# 7805.net
KiCad netlist of a schematic drawn in EAGLE
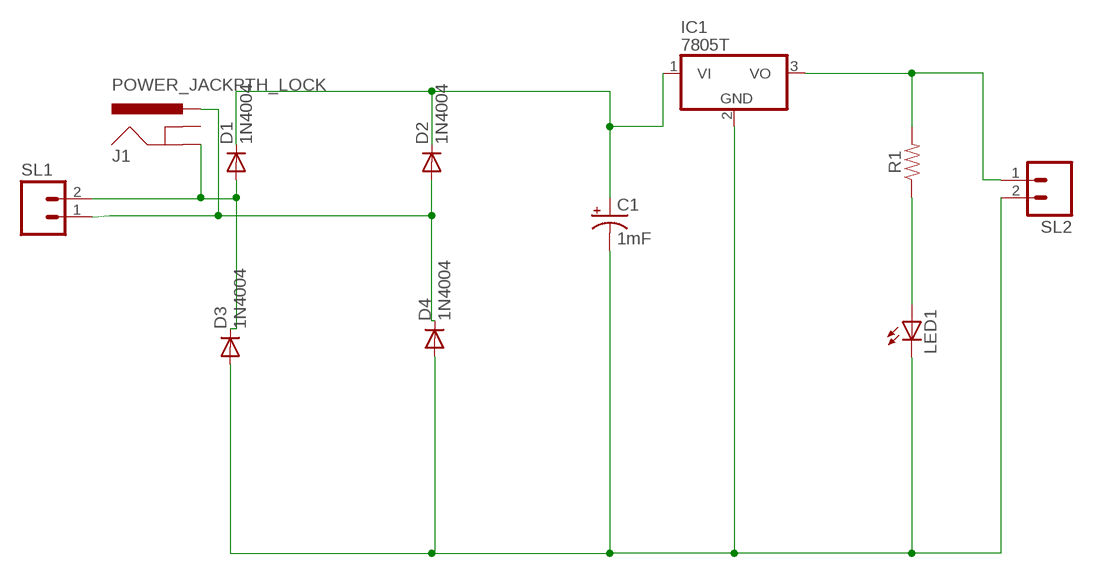
[diagram p0: schematic, sheet 1]

(export (version "E")
  (design (tool "Eeschema 10.0.6"))
  (components
    (comp (ref "C1")
      (value "1mF")
      (footprint "eagle-import:CPOL-RADIAL-5MM-10MM")
      (libsource (lib "eagle-import") (part "1000UF-RADIAL-5MM-25V-20%"))
    )
    (comp (ref "D1")
      (value "1N4004")
      (footprint "eagle-import:DO41-10")
      (libsource (lib "eagle-import") (part "1N4004"))
    )
    (comp (ref "D2")
      (value "1N4004")
      (footprint "eagle-import:DO41-10")
      (libsource (lib "eagle-import") (part "1N4004"))
    )
    (comp (ref "D3")
      (value "1N4004")
      (footprint "eagle-import:DO41-10")
      (libsource (lib "eagle-import") (part "1N4004"))
    )
    (comp (ref "D4")
      (value "1N4004")
      (footprint "eagle-import:DO41-10")
      (libsource (lib "eagle-import") (part "1N4004"))
    )
    (comp (ref "IC1")
      (value "7805T")
      (footprint "eagle-import:TO220H")
      (libsource (lib "eagle-import") (part "78T05"))
    )
    (comp (ref "J1")
      (value "POWER_JACKPTH_LOCK")
      (footprint "eagle-import:POWER_JACK_PTH_LOCK")
      (libsource (lib "eagle-import") (part "POWER_JACKPTH_LOCK"))
    )
    (comp (ref "LED1")
      (value "LED5MM")
      (footprint "eagle-import:LED5MM")
      (libsource (lib "eagle-import") (part "LED5MM"))
    )
    (comp (ref "R1")
      (value "RESISTORAXIAL-0.3")
      (footprint "eagle-import:AXIAL-0.3")
      (libsource (lib "eagle-import") (part "RESISTORAXIAL-0.3"))
    )
    (comp (ref "SL1")
      (value "M02")
      (footprint "eagle-import:02P")
      (libsource (lib "eagle-import") (part "M02"))
    )
    (comp (ref "SL2")
      (value "M02")
      (footprint "eagle-import:02P")
      (libsource (lib "eagle-import") (part "M02"))
    )
  )
  (nets
    (net (code "1") (name "Net-(D1-PadA)") (class "Default")
      (node (ref "D1") (pin "A") (pinfunction "A_A") (pintype "passive"))
      (node (ref "D3") (pin "C") (pinfunction "C_C") (pintype "passive"))
      (node (ref "SL1") (pin "2") (pinfunction "2_2") (pintype "passive"))
    )
    (net (code "2") (name "Net-(D2-PadA)") (class "Default")
      (node (ref "D2") (pin "A") (pinfunction "A_A") (pintype "passive"))
      (node (ref "D4") (pin "C") (pinfunction "C_C") (pintype "passive"))
      (node (ref "J1") (pin "PWR") (pinfunction "PWR_PWR") (pintype "bidirectional"))
      (node (ref "SL1") (pin "1") (pinfunction "1_1") (pintype "passive"))
    )
    (net (code "3") (name "Net-(IC1-GND)") (class "Default")
      (node (ref "C1") (pin "-") (pinfunction "-_-") (pintype "passive"))
      (node (ref "D3") (pin "A") (pinfunction "A_A") (pintype "passive"))
      (node (ref "IC1") (pin "2") (pinfunction "GND_2") (pintype "passive"))
      (node (ref "LED1") (pin "K") (pinfunction "C_K") (pintype "passive"))
      (node (ref "SL2") (pin "2") (pinfunction "2_2") (pintype "passive"))
    )
    (net (code "4") (name "Net-(IC1-VI)") (class "Default")
      (node (ref "C1") (pin "+") (pinfunction "+_+") (pintype "passive"))
      (node (ref "D1") (pin "C") (pinfunction "C_C") (pintype "passive"))
      (node (ref "D2") (pin "C") (pinfunction "C_C") (pintype "passive"))
      (node (ref "IC1") (pin "1") (pinfunction "VI_1") (pintype "input"))
    )
    (net (code "5") (name "Net-(IC1-VO)") (class "Default")
      (node (ref "IC1") (pin "3") (pinfunction "VO_3") (pintype "passive"))
      (node (ref "R1") (pin "P$2") (pinfunction "2_P$2") (pintype "passive"))
      (node (ref "SL2") (pin "1") (pinfunction "1_1") (pintype "passive"))
    )
    (net (code "6") (name "Net-(R1-1)") (class "Default")
      (node (ref "LED1") (pin "A") (pinfunction "A_A") (pintype "passive"))
      (node (ref "R1") (pin "P$1") (pinfunction "1_P$1") (pintype "passive"))
    )
    (net (code "7") (name "unconnected-(D4-PadA)") (class "Default")
      (node (ref "D4") (pin "A") (pinfunction "A_A") (pintype "passive"))
    )
    (net (code "8") (name "unconnected-(J1-PadGND)") (class "Default")
      (node (ref "J1") (pin "GND") (pinfunction "GND_GND") (pintype "bidirectional"))
    )
    (net (code "9") (name "unconnected-(J1-PadGNDBREAK)") (class "Default")
      (node (ref "J1") (pin "GNDBREAK") (pinfunction "GNDBREAK_GNDBREAK") (pintype "bidirectional"))
    )
  )
)
